# Isolator_14.net
KiCad netlist of a schematic drawn in EAGLE
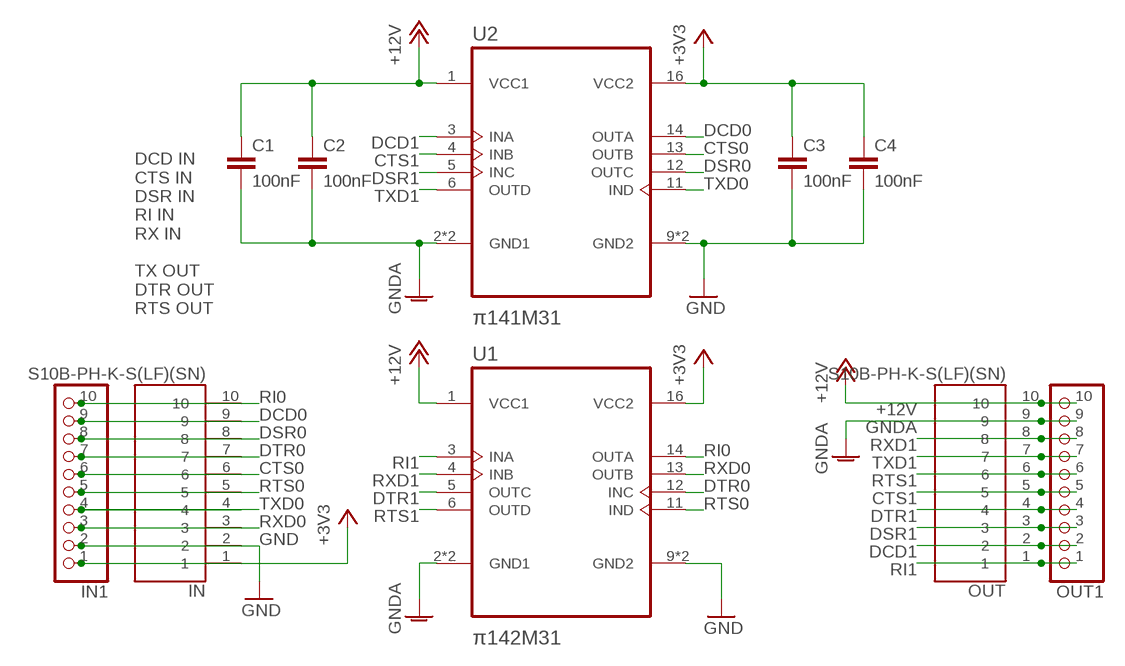
[diagram p0: schematic, sheet 1]

(export (version "E")
  (design (tool "Eeschema 10.0.6"))
  (components
    (comp (ref "C1")
      (value "100nF")
      (footprint "eagle-import:C0805")
      (libsource (lib "eagle-import") (part "C-EUC0805"))
    )
    (comp (ref "C2")
      (value "100nF")
      (footprint "eagle-import:C0805")
      (libsource (lib "eagle-import") (part "C-EUC0805"))
    )
    (comp (ref "C3")
      (value "100nF")
      (footprint "eagle-import:C0805")
      (libsource (lib "eagle-import") (part "C-EUC0805"))
    )
    (comp (ref "C4")
      (value "100nF")
      (footprint "eagle-import:C0805")
      (libsource (lib "eagle-import") (part "C-EUC0805"))
    )
    (comp (ref "IN")
      (value "S10B-PH-K-S(LF)(SN)")
      (footprint "eagle-import:JST_S10B-PH-K-S(LF)(SN)")
      (fields (field (name "MF") "JST Sales") (field (name "MP") "S6B-PH-K-S(LF)(SN)"))
      (libsource (lib "eagle-import") (part "S10B-PH-K-S(LF)(SN)"))
    )
    (comp (ref "IN1")
      (value "PINHD-1X10")
      (footprint "eagle-import:1X10")
      (libsource (lib "eagle-import") (part "PINHD-1X10"))
    )
    (comp (ref "OUT")
      (value "S10B-PH-K-S(LF)(SN)")
      (footprint "eagle-import:JST_S10B-PH-K-S(LF)(SN)")
      (fields (field (name "MF") "JST Sales") (field (name "MP") "S6B-PH-K-S(LF)(SN)"))
      (libsource (lib "eagle-import") (part "S10B-PH-K-S(LF)(SN)"))
    )
    (comp (ref "OUT1")
      (value "PINHD-1X10")
      (footprint "eagle-import:1X10")
      (libsource (lib "eagle-import") (part "PINHD-1X10"))
    )
    (comp (ref "U1")
      (value "π142M31")
      (footprint "eagle-import:SOIC-16")
      (fields (field (name "MF") "Texas Instruments") (field (name "MP") "ISO7240CDWR"))
      (libsource (lib "eagle-import") (part "π142X3X"))
    )
    (comp (ref "U2")
      (value "π141M31")
      (footprint "eagle-import:SOIC-16")
      (fields (field (name "MF") "Texas Instruments") (field (name "MP") "ISO7240CDWR"))
      (libsource (lib "eagle-import") (part "π141X3X"))
    )
  )
  (nets
    (net (code "1") (name "+3V3") (class "Default")
      (node (ref "C3") (pin "1") (pinfunction "1_1") (pintype "passive"))
      (node (ref "C4") (pin "1") (pinfunction "1_1") (pintype "passive"))
      (node (ref "IN") (pin "1") (pinfunction "1_1") (pintype "passive"))
      (node (ref "IN1") (pin "1") (pinfunction "1_1") (pintype "passive"))
      (node (ref "U1") (pin "16") (pinfunction "VCC2_16") (pintype "power_in"))
      (node (ref "U2") (pin "16") (pinfunction "VCC2_16") (pintype "power_in"))
    )
    (net (code "2") (name "+12V") (class "Default")
      (node (ref "C1") (pin "1") (pinfunction "1_1") (pintype "passive"))
      (node (ref "C2") (pin "1") (pinfunction "1_1") (pintype "passive"))
      (node (ref "OUT") (pin "10") (pinfunction "10_10") (pintype "passive"))
      (node (ref "OUT1") (pin "10") (pinfunction "10_10") (pintype "passive"))
      (node (ref "U1") (pin "1") (pinfunction "VCC1_1") (pintype "power_in"))
      (node (ref "U2") (pin "1") (pinfunction "VCC1_1") (pintype "power_in"))
    )
    (net (code "3") (name "/CTS0") (class "Default")
      (node (ref "IN") (pin "6") (pinfunction "6_6") (pintype "passive"))
      (node (ref "IN1") (pin "6") (pinfunction "6_6") (pintype "passive"))
      (node (ref "U2") (pin "13") (pinfunction "OUTB_13") (pintype "output"))
    )
    (net (code "4") (name "/CTS1") (class "Default")
      (node (ref "OUT") (pin "5") (pinfunction "5_5") (pintype "passive"))
      (node (ref "OUT1") (pin "5") (pinfunction "5_5") (pintype "passive"))
      (node (ref "U2") (pin "4") (pinfunction "INB_4") (pintype "input"))
    )
    (net (code "5") (name "/DCD0") (class "Default")
      (node (ref "IN") (pin "9") (pinfunction "9_9") (pintype "passive"))
      (node (ref "IN1") (pin "9") (pinfunction "9_9") (pintype "passive"))
      (node (ref "U2") (pin "14") (pinfunction "OUTA_14") (pintype "output"))
    )
    (net (code "6") (name "/DCD1") (class "Default")
      (node (ref "OUT") (pin "2") (pinfunction "2_2") (pintype "passive"))
      (node (ref "OUT1") (pin "2") (pinfunction "2_2") (pintype "passive"))
      (node (ref "U2") (pin "3") (pinfunction "INA_3") (pintype "input"))
    )
    (net (code "7") (name "/DSR0") (class "Default")
      (node (ref "IN") (pin "8") (pinfunction "8_8") (pintype "passive"))
      (node (ref "IN1") (pin "8") (pinfunction "8_8") (pintype "passive"))
      (node (ref "U2") (pin "12") (pinfunction "OUTC_12") (pintype "output"))
    )
    (net (code "8") (name "/DSR1") (class "Default")
      (node (ref "OUT") (pin "3") (pinfunction "3_3") (pintype "passive"))
      (node (ref "OUT1") (pin "3") (pinfunction "3_3") (pintype "passive"))
      (node (ref "U2") (pin "5") (pinfunction "INC_5") (pintype "input"))
    )
    (net (code "9") (name "/DTR0") (class "Default")
      (node (ref "IN") (pin "7") (pinfunction "7_7") (pintype "passive"))
      (node (ref "IN1") (pin "7") (pinfunction "7_7") (pintype "passive"))
      (node (ref "U1") (pin "12") (pinfunction "INC_12") (pintype "input"))
    )
    (net (code "10") (name "/DTR1") (class "Default")
      (node (ref "OUT") (pin "4") (pinfunction "4_4") (pintype "passive"))
      (node (ref "OUT1") (pin "4") (pinfunction "4_4") (pintype "passive"))
      (node (ref "U1") (pin "5") (pinfunction "OUTC_5") (pintype "output"))
    )
    (net (code "11") (name "/RI0") (class "Default")
      (node (ref "IN") (pin "10") (pinfunction "10_10") (pintype "passive"))
      (node (ref "IN1") (pin "10") (pinfunction "10_10") (pintype "passive"))
      (node (ref "U1") (pin "14") (pinfunction "OUTA_14") (pintype "output"))
    )
    (net (code "12") (name "/RI1") (class "Default")
      (node (ref "OUT") (pin "1") (pinfunction "1_1") (pintype "passive"))
      (node (ref "OUT1") (pin "1") (pinfunction "1_1") (pintype "passive"))
      (node (ref "U1") (pin "3") (pinfunction "INA_3") (pintype "input"))
    )
    (net (code "13") (name "/RTS0") (class "Default")
      (node (ref "IN") (pin "5") (pinfunction "5_5") (pintype "passive"))
      (node (ref "IN1") (pin "5") (pinfunction "5_5") (pintype "passive"))
      (node (ref "U1") (pin "11") (pinfunction "IND_11") (pintype "input"))
    )
    (net (code "14") (name "/RTS1") (class "Default")
      (node (ref "OUT") (pin "6") (pinfunction "6_6") (pintype "passive"))
      (node (ref "OUT1") (pin "6") (pinfunction "6_6") (pintype "passive"))
      (node (ref "U1") (pin "6") (pinfunction "OUTD_6") (pintype "output"))
    )
    (net (code "15") (name "/RXD0") (class "Default")
      (node (ref "IN") (pin "3") (pinfunction "3_3") (pintype "passive"))
      (node (ref "IN1") (pin "3") (pinfunction "3_3") (pintype "passive"))
      (node (ref "U1") (pin "13") (pinfunction "OUTB_13") (pintype "output"))
    )
    (net (code "16") (name "/RXD1") (class "Default")
      (node (ref "OUT") (pin "8") (pinfunction "8_8") (pintype "passive"))
      (node (ref "OUT1") (pin "8") (pinfunction "8_8") (pintype "passive"))
      (node (ref "U1") (pin "4") (pinfunction "INB_4") (pintype "input"))
    )
    (net (code "17") (name "/TXD0") (class "Default")
      (node (ref "IN") (pin "4") (pinfunction "4_4") (pintype "passive"))
      (node (ref "IN1") (pin "4") (pinfunction "4_4") (pintype "passive"))
      (node (ref "U2") (pin "11") (pinfunction "IND_11") (pintype "input"))
    )
    (net (code "18") (name "/TXD1") (class "Default")
      (node (ref "OUT") (pin "7") (pinfunction "7_7") (pintype "passive"))
      (node (ref "OUT1") (pin "7") (pinfunction "7_7") (pintype "passive"))
      (node (ref "U2") (pin "6") (pinfunction "OUTD_6") (pintype "output"))
    )
    (net (code "19") (name "GND") (class "Default")
      (node (ref "C3") (pin "2") (pinfunction "2_2") (pintype "passive"))
      (node (ref "C4") (pin "2") (pinfunction "2_2") (pintype "passive"))
      (node (ref "IN") (pin "2") (pinfunction "2_2") (pintype "passive"))
      (node (ref "IN1") (pin "2") (pinfunction "2_2") (pintype "passive"))
      (node (ref "U1") (pin "15") (pinfunction "GND2_15") (pintype "power_in"))
      (node (ref "U1") (pin "9") (pinfunction "GND2_9") (pintype "power_in"))
      (node (ref "U2") (pin "15") (pinfunction "GND2_15") (pintype "power_in"))
      (node (ref "U2") (pin "9") (pinfunction "GND2_9") (pintype "power_in"))
    )
    (net (code "20") (name "GNDA") (class "Default")
      (node (ref "C1") (pin "2") (pinfunction "2_2") (pintype "passive"))
      (node (ref "C2") (pin "2") (pinfunction "2_2") (pintype "passive"))
      (node (ref "OUT") (pin "9") (pinfunction "9_9") (pintype "passive"))
      (node (ref "OUT1") (pin "9") (pinfunction "9_9") (pintype "passive"))
      (node (ref "U1") (pin "2") (pinfunction "GND1_2") (pintype "power_in"))
      (node (ref "U1") (pin "8") (pinfunction "GND1_8") (pintype "power_in"))
      (node (ref "U2") (pin "2") (pinfunction "GND1_2") (pintype "power_in"))
      (node (ref "U2") (pin "8") (pinfunction "GND1_8") (pintype "power_in"))
    )
  )
)
